# ddrive-esp-deadrail-1-7-routed.net
KiCad netlist of a schematic drawn in EAGLE
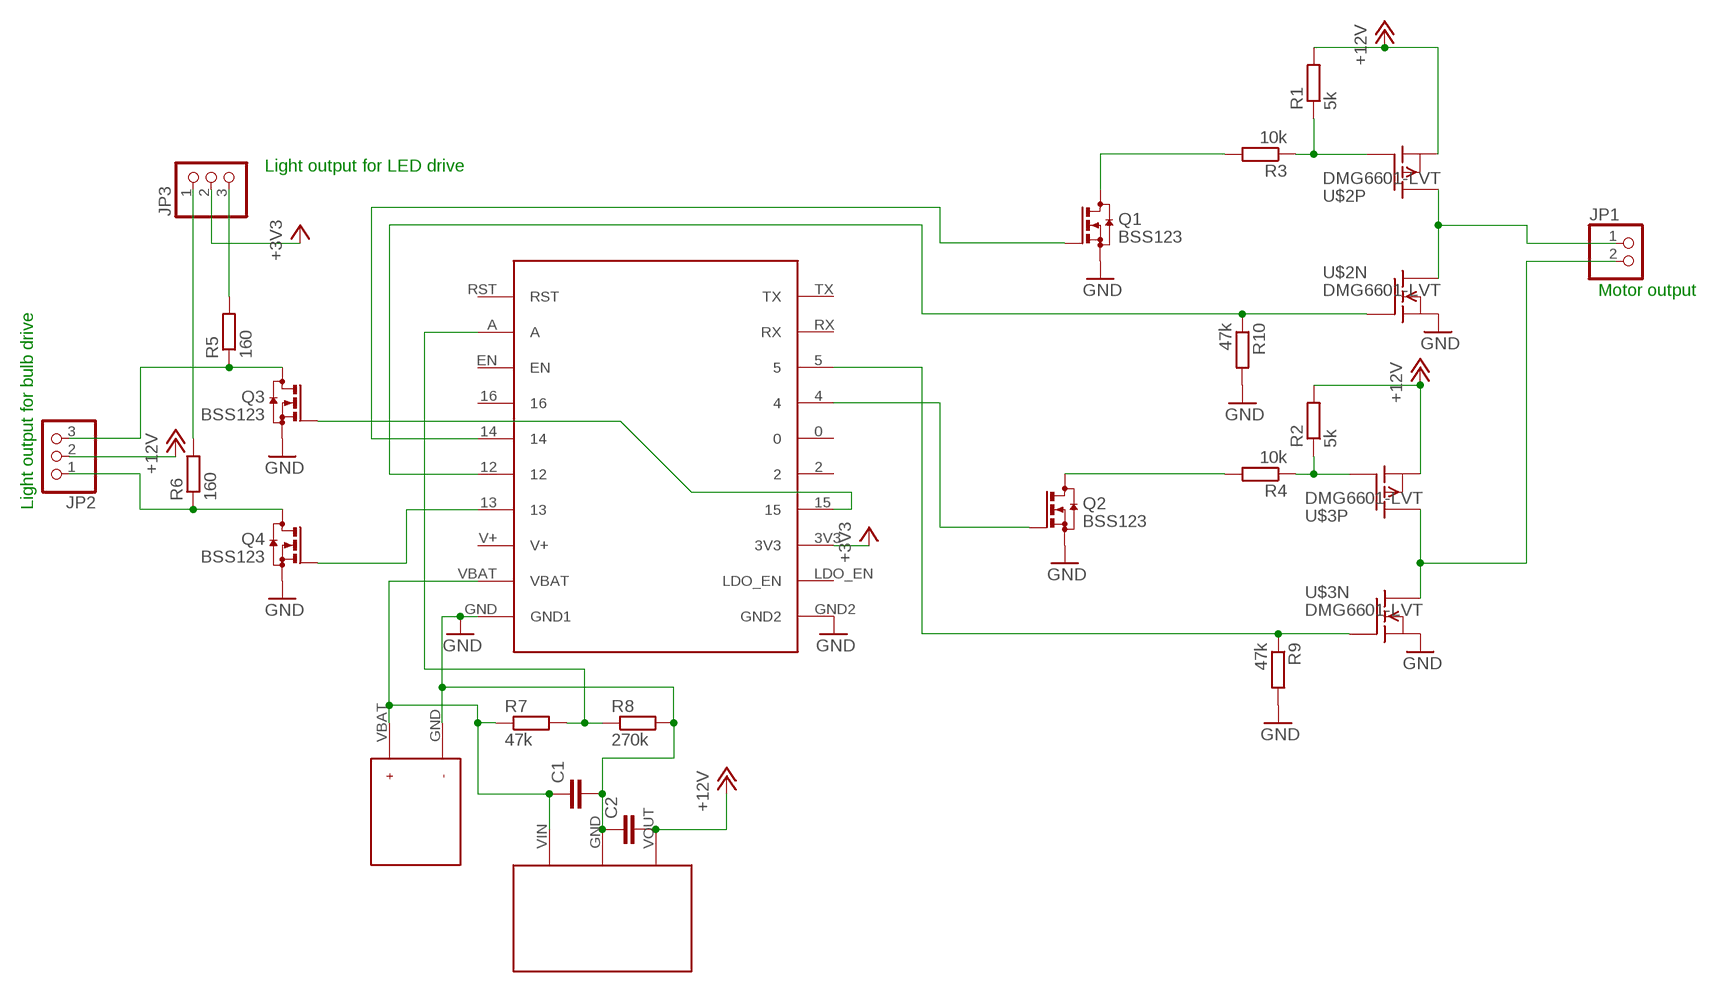
[diagram p0: schematic, sheet 1]

(export (version "E")
  (design (tool "Eeschema 10.0.6"))
  (components
    (comp (ref "C1")
      (value "C-EUC1210")
      (footprint "eagle-import:C1210")
      (libsource (lib "eagle-import") (part "C-EUC1210"))
    )
    (comp (ref "C2")
      (value "C-EUC1210")
      (footprint "eagle-import:C1210")
      (libsource (lib "eagle-import") (part "C-EUC1210"))
    )
    (comp (ref "JP1")
      (value "PINHD-1X2")
      (footprint "eagle-import:1X02")
      (libsource (lib "eagle-import") (part "PINHD-1X2"))
    )
    (comp (ref "JP2")
      (value "PINHD-1X3")
      (footprint "eagle-import:1X03")
      (libsource (lib "eagle-import") (part "PINHD-1X3"))
    )
    (comp (ref "JP3")
      (value "PINHD-1X3")
      (footprint "eagle-import:1X03")
      (libsource (lib "eagle-import") (part "PINHD-1X3"))
    )
    (comp (ref "Q1")
      (value "BSS123")
      (footprint "eagle-import:SOT23")
      (libsource (lib "eagle-import") (part "BSS123"))
    )
    (comp (ref "Q2")
      (value "BSS123")
      (footprint "eagle-import:SOT23")
      (libsource (lib "eagle-import") (part "BSS123"))
    )
    (comp (ref "Q3")
      (value "BSS123")
      (footprint "eagle-import:SOT23")
      (libsource (lib "eagle-import") (part "BSS123"))
    )
    (comp (ref "Q4")
      (value "BSS123")
      (footprint "eagle-import:SOT23")
      (libsource (lib "eagle-import") (part "BSS123"))
    )
    (comp (ref "R1")
      (value "5k")
      (footprint "eagle-import:R0805")
      (libsource (lib "eagle-import") (part "R-EU_R0805"))
    )
    (comp (ref "R2")
      (value "5k")
      (footprint "eagle-import:R0805")
      (libsource (lib "eagle-import") (part "R-EU_R0805"))
    )
    (comp (ref "R3")
      (value "10k")
      (footprint "eagle-import:R0805")
      (libsource (lib "eagle-import") (part "R-EU_R0805"))
    )
    (comp (ref "R4")
      (value "10k")
      (footprint "eagle-import:R0805")
      (libsource (lib "eagle-import") (part "R-EU_R0805"))
    )
    (comp (ref "R5")
      (value "160")
      (footprint "eagle-import:R0805")
      (libsource (lib "eagle-import") (part "R-EU_R0805"))
    )
    (comp (ref "R6")
      (value "160")
      (footprint "eagle-import:R0805")
      (libsource (lib "eagle-import") (part "R-EU_R0805"))
    )
    (comp (ref "R7")
      (value "47k")
      (footprint "eagle-import:R0805")
      (libsource (lib "eagle-import") (part "R-EU_R0805"))
    )
    (comp (ref "R8")
      (value "270k")
      (footprint "eagle-import:R0805")
      (libsource (lib "eagle-import") (part "R-EU_R0805"))
    )
    (comp (ref "R9")
      (value "47k")
      (footprint "eagle-import:R0805")
      (libsource (lib "eagle-import") (part "R-EU_R0805"))
    )
    (comp (ref "R10")
      (value "47k")
      (footprint "eagle-import:R0805")
      (libsource (lib "eagle-import") (part "R-EU_R0805"))
    )
    (comp (ref "U$1")
      (value "ESP12-HUZZAH")
      (footprint "eagle-import:ESP12-HUZZAH")
      (libsource (lib "eagle-import") (part "ESP12-HUZZAH"))
    )
    (comp (ref "U$2")
      (value "DMG6601-LVT")
      (footprint "eagle-import:TSOT-26")
      (libsource (lib "eagle-import") (part "DMG6601-LVT"))
    )
    (comp (ref "U$3")
      (value "DMG6601-LVT")
      (footprint "eagle-import:TSOT-26")
      (libsource (lib "eagle-import") (part "DMG6601-LVT"))
    )
    (comp (ref "U$4")
      (value "JST-PINHD")
      (footprint "eagle-import:JST-PINHDR")
      (libsource (lib "eagle-import") (part "JST-PINHD"))
    )
    (comp (ref "U$5")
      (value "POLOLU-VREG12")
      (footprint "eagle-import:POLOLU-REGULATOR")
      (libsource (lib "eagle-import") (part "POLOLU-VREG12"))
    )
  )
  (nets
    (net (code "1") (name "+3V3") (class "Default")
      (node (ref "JP3") (pin "2") (pinfunction "2_2") (pintype "passive"))
      (node (ref "U$1") (pin "3V3") (pinfunction "3V3_3V3") (pintype "power_in"))
    )
    (net (code "2") (name "+12V") (class "Default")
      (node (ref "C2") (pin "2") (pinfunction "2_2") (pintype "passive"))
      (node (ref "JP2") (pin "2") (pinfunction "2_2") (pintype "passive"))
      (node (ref "R1") (pin "2") (pinfunction "2_2") (pintype "passive"))
      (node (ref "R2") (pin "2") (pinfunction "2_2") (pintype "passive"))
      (node (ref "U$2") (pin "2") (pinfunction "S_2") (pintype "passive"))
      (node (ref "U$3") (pin "2") (pinfunction "S_2") (pintype "passive"))
      (node (ref "U$5") (pin "VOUT") (pinfunction "VOUT_VOUT") (pintype "bidirectional"))
    )
    (net (code "3") (name "/V+") (class "Default")
      (node (ref "U$1") (pin "V+") (pinfunction "V+_V+") (pintype "power_in"))
    )
    (net (code "4") (name "GND") (class "Default")
      (node (ref "C1") (pin "2") (pinfunction "2_2") (pintype "passive"))
      (node (ref "C2") (pin "1") (pinfunction "1_1") (pintype "passive"))
      (node (ref "Q1") (pin "2") (pinfunction "S_2") (pintype "passive"))
      (node (ref "Q2") (pin "2") (pinfunction "S_2") (pintype "passive"))
      (node (ref "Q3") (pin "2") (pinfunction "S_2") (pintype "passive"))
      (node (ref "Q4") (pin "2") (pinfunction "S_2") (pintype "passive"))
      (node (ref "R10") (pin "2") (pinfunction "2_2") (pintype "passive"))
      (node (ref "R8") (pin "2") (pinfunction "2_2") (pintype "passive"))
      (node (ref "R9") (pin "2") (pinfunction "2_2") (pintype "passive"))
      (node (ref "U$1") (pin "GND") (pinfunction "GND1_GND") (pintype "power_in"))
      (node (ref "U$1") (pin "GND2") (pinfunction "GND2_GND2") (pintype "power_in"))
      (node (ref "U$2") (pin "5") (pinfunction "S_5") (pintype "passive"))
      (node (ref "U$3") (pin "5") (pinfunction "S_5") (pintype "passive"))
      (node (ref "U$4") (pin "GND") (pinfunction "P$1_GND") (pintype "power_in"))
      (node (ref "U$5") (pin "GND") (pinfunction "GND_GND") (pintype "bidirectional"))
    )
    (net (code "5") (name "Net-(JP3-Pad1)") (class "Default")
      (node (ref "JP3") (pin "1") (pinfunction "1_1") (pintype "passive"))
      (node (ref "R6") (pin "2") (pinfunction "2_2") (pintype "passive"))
    )
    (net (code "6") (name "Net-(JP3-Pad3)") (class "Default")
      (node (ref "JP3") (pin "3") (pinfunction "3_3") (pintype "passive"))
      (node (ref "R5") (pin "2") (pinfunction "2_2") (pintype "passive"))
    )
    (net (code "7") (name "Net-(Q1-D)") (class "Default")
      (node (ref "Q1") (pin "3") (pinfunction "D_3") (pintype "passive"))
      (node (ref "R3") (pin "2") (pinfunction "2_2") (pintype "passive"))
    )
    (net (code "8") (name "Net-(Q1-G)") (class "Default")
      (node (ref "Q1") (pin "1") (pinfunction "G_1") (pintype "passive"))
      (node (ref "U$1") (pin "14") (pinfunction "14_14") (pintype "bidirectional"))
    )
    (net (code "9") (name "Net-(Q2-D)") (class "Default")
      (node (ref "Q2") (pin "3") (pinfunction "D_3") (pintype "passive"))
      (node (ref "R4") (pin "2") (pinfunction "2_2") (pintype "passive"))
    )
    (net (code "10") (name "Net-(Q2-G)") (class "Default")
      (node (ref "Q2") (pin "1") (pinfunction "G_1") (pintype "passive"))
      (node (ref "U$1") (pin "4") (pinfunction "4_4") (pintype "bidirectional"))
    )
    (net (code "11") (name "Net-(Q3-D)") (class "Default")
      (node (ref "JP2") (pin "3") (pinfunction "3_3") (pintype "passive"))
      (node (ref "Q3") (pin "3") (pinfunction "D_3") (pintype "passive"))
      (node (ref "R5") (pin "1") (pinfunction "1_1") (pintype "passive"))
    )
    (net (code "12") (name "Net-(Q3-G)") (class "Default")
      (node (ref "Q3") (pin "1") (pinfunction "G_1") (pintype "passive"))
      (node (ref "U$1") (pin "15") (pinfunction "15_15") (pintype "bidirectional"))
    )
    (net (code "13") (name "Net-(Q4-D)") (class "Default")
      (node (ref "JP2") (pin "1") (pinfunction "1_1") (pintype "passive"))
      (node (ref "Q4") (pin "3") (pinfunction "D_3") (pintype "passive"))
      (node (ref "R6") (pin "1") (pinfunction "1_1") (pintype "passive"))
    )
    (net (code "14") (name "Net-(Q4-G)") (class "Default")
      (node (ref "Q4") (pin "1") (pinfunction "G_1") (pintype "passive"))
      (node (ref "U$1") (pin "13") (pinfunction "13_13") (pintype "bidirectional"))
    )
    (net (code "15") (name "Net-(R7-Pad2)") (class "Default")
      (node (ref "R7") (pin "2") (pinfunction "2_2") (pintype "passive"))
      (node (ref "R8") (pin "1") (pinfunction "1_1") (pintype "passive"))
      (node (ref "U$1") (pin "A") (pinfunction "A_A") (pintype "bidirectional"))
    )
    (net (code "16") (name "Net-(U$2A-D)") (class "Default")
      (node (ref "JP1") (pin "1") (pinfunction "1_1") (pintype "passive"))
      (node (ref "U$2") (pin "4") (pinfunction "D_4") (pintype "passive"))
      (node (ref "U$2") (pin "6") (pinfunction "D_6") (pintype "passive"))
    )
    (net (code "17") (name "Net-(U$2A-G)") (class "Default")
      (node (ref "R10") (pin "1") (pinfunction "1_1") (pintype "passive"))
      (node (ref "U$1") (pin "12") (pinfunction "12_12") (pintype "bidirectional"))
      (node (ref "U$2") (pin "1") (pinfunction "G_1") (pintype "passive"))
    )
    (net (code "18") (name "Net-(U$2B-G)") (class "Default")
      (node (ref "R1") (pin "1") (pinfunction "1_1") (pintype "passive"))
      (node (ref "R3") (pin "1") (pinfunction "1_1") (pintype "passive"))
      (node (ref "U$2") (pin "3") (pinfunction "G_3") (pintype "passive"))
    )
    (net (code "19") (name "Net-(U$3A-D)") (class "Default")
      (node (ref "JP1") (pin "2") (pinfunction "2_2") (pintype "passive"))
      (node (ref "U$3") (pin "4") (pinfunction "D_4") (pintype "passive"))
      (node (ref "U$3") (pin "6") (pinfunction "D_6") (pintype "passive"))
    )
    (net (code "20") (name "Net-(U$3A-G)") (class "Default")
      (node (ref "R9") (pin "1") (pinfunction "1_1") (pintype "passive"))
      (node (ref "U$1") (pin "5") (pinfunction "5_5") (pintype "bidirectional"))
      (node (ref "U$3") (pin "1") (pinfunction "G_1") (pintype "passive"))
    )
    (net (code "21") (name "Net-(U$3B-G)") (class "Default")
      (node (ref "R2") (pin "1") (pinfunction "1_1") (pintype "passive"))
      (node (ref "R4") (pin "1") (pinfunction "1_1") (pintype "passive"))
      (node (ref "U$3") (pin "3") (pinfunction "G_3") (pintype "passive"))
    )
    (net (code "22") (name "Net-(U$4-P$2)") (class "Default")
      (node (ref "C1") (pin "1") (pinfunction "1_1") (pintype "passive"))
      (node (ref "R7") (pin "1") (pinfunction "1_1") (pintype "passive"))
      (node (ref "U$1") (pin "VBAT") (pinfunction "VBAT_VBAT") (pintype "power_in"))
      (node (ref "U$4") (pin "VBAT") (pinfunction "P$2_VBAT") (pintype "power_in"))
      (node (ref "U$5") (pin "VIN") (pinfunction "VIN_VIN") (pintype "bidirectional"))
    )
    (net (code "23") (name "unconnected-(U$1-Pad0)") (class "Default")
      (node (ref "U$1") (pin "0") (pinfunction "0_0") (pintype "bidirectional"))
    )
    (net (code "24") (name "unconnected-(U$1-Pad2)") (class "Default")
      (node (ref "U$1") (pin "2") (pinfunction "2_2") (pintype "bidirectional"))
    )
    (net (code "25") (name "unconnected-(U$1-Pad16)") (class "Default")
      (node (ref "U$1") (pin "16") (pinfunction "16_16") (pintype "bidirectional"))
    )
    (net (code "26") (name "unconnected-(U$1-PadEN)") (class "Default")
      (node (ref "U$1") (pin "EN") (pinfunction "EN_EN") (pintype "bidirectional"))
    )
    (net (code "27") (name "unconnected-(U$1-PadLDO_EN)") (class "Default")
      (node (ref "U$1") (pin "LDO_EN") (pinfunction "LDO_EN_LDO_EN") (pintype "bidirectional"))
    )
    (net (code "28") (name "unconnected-(U$1-PadRST)") (class "Default")
      (node (ref "U$1") (pin "RST") (pinfunction "RST_RST") (pintype "bidirectional"))
    )
    (net (code "29") (name "unconnected-(U$1-PadRX)") (class "Default")
      (node (ref "U$1") (pin "RX") (pinfunction "RX_RX") (pintype "bidirectional"))
    )
    (net (code "30") (name "unconnected-(U$1-PadTX)") (class "Default")
      (node (ref "U$1") (pin "TX") (pinfunction "TX_TX") (pintype "bidirectional"))
    )
  )
)
